# ArtFire.net
KiCad netlist of a schematic drawn in Altium Designer
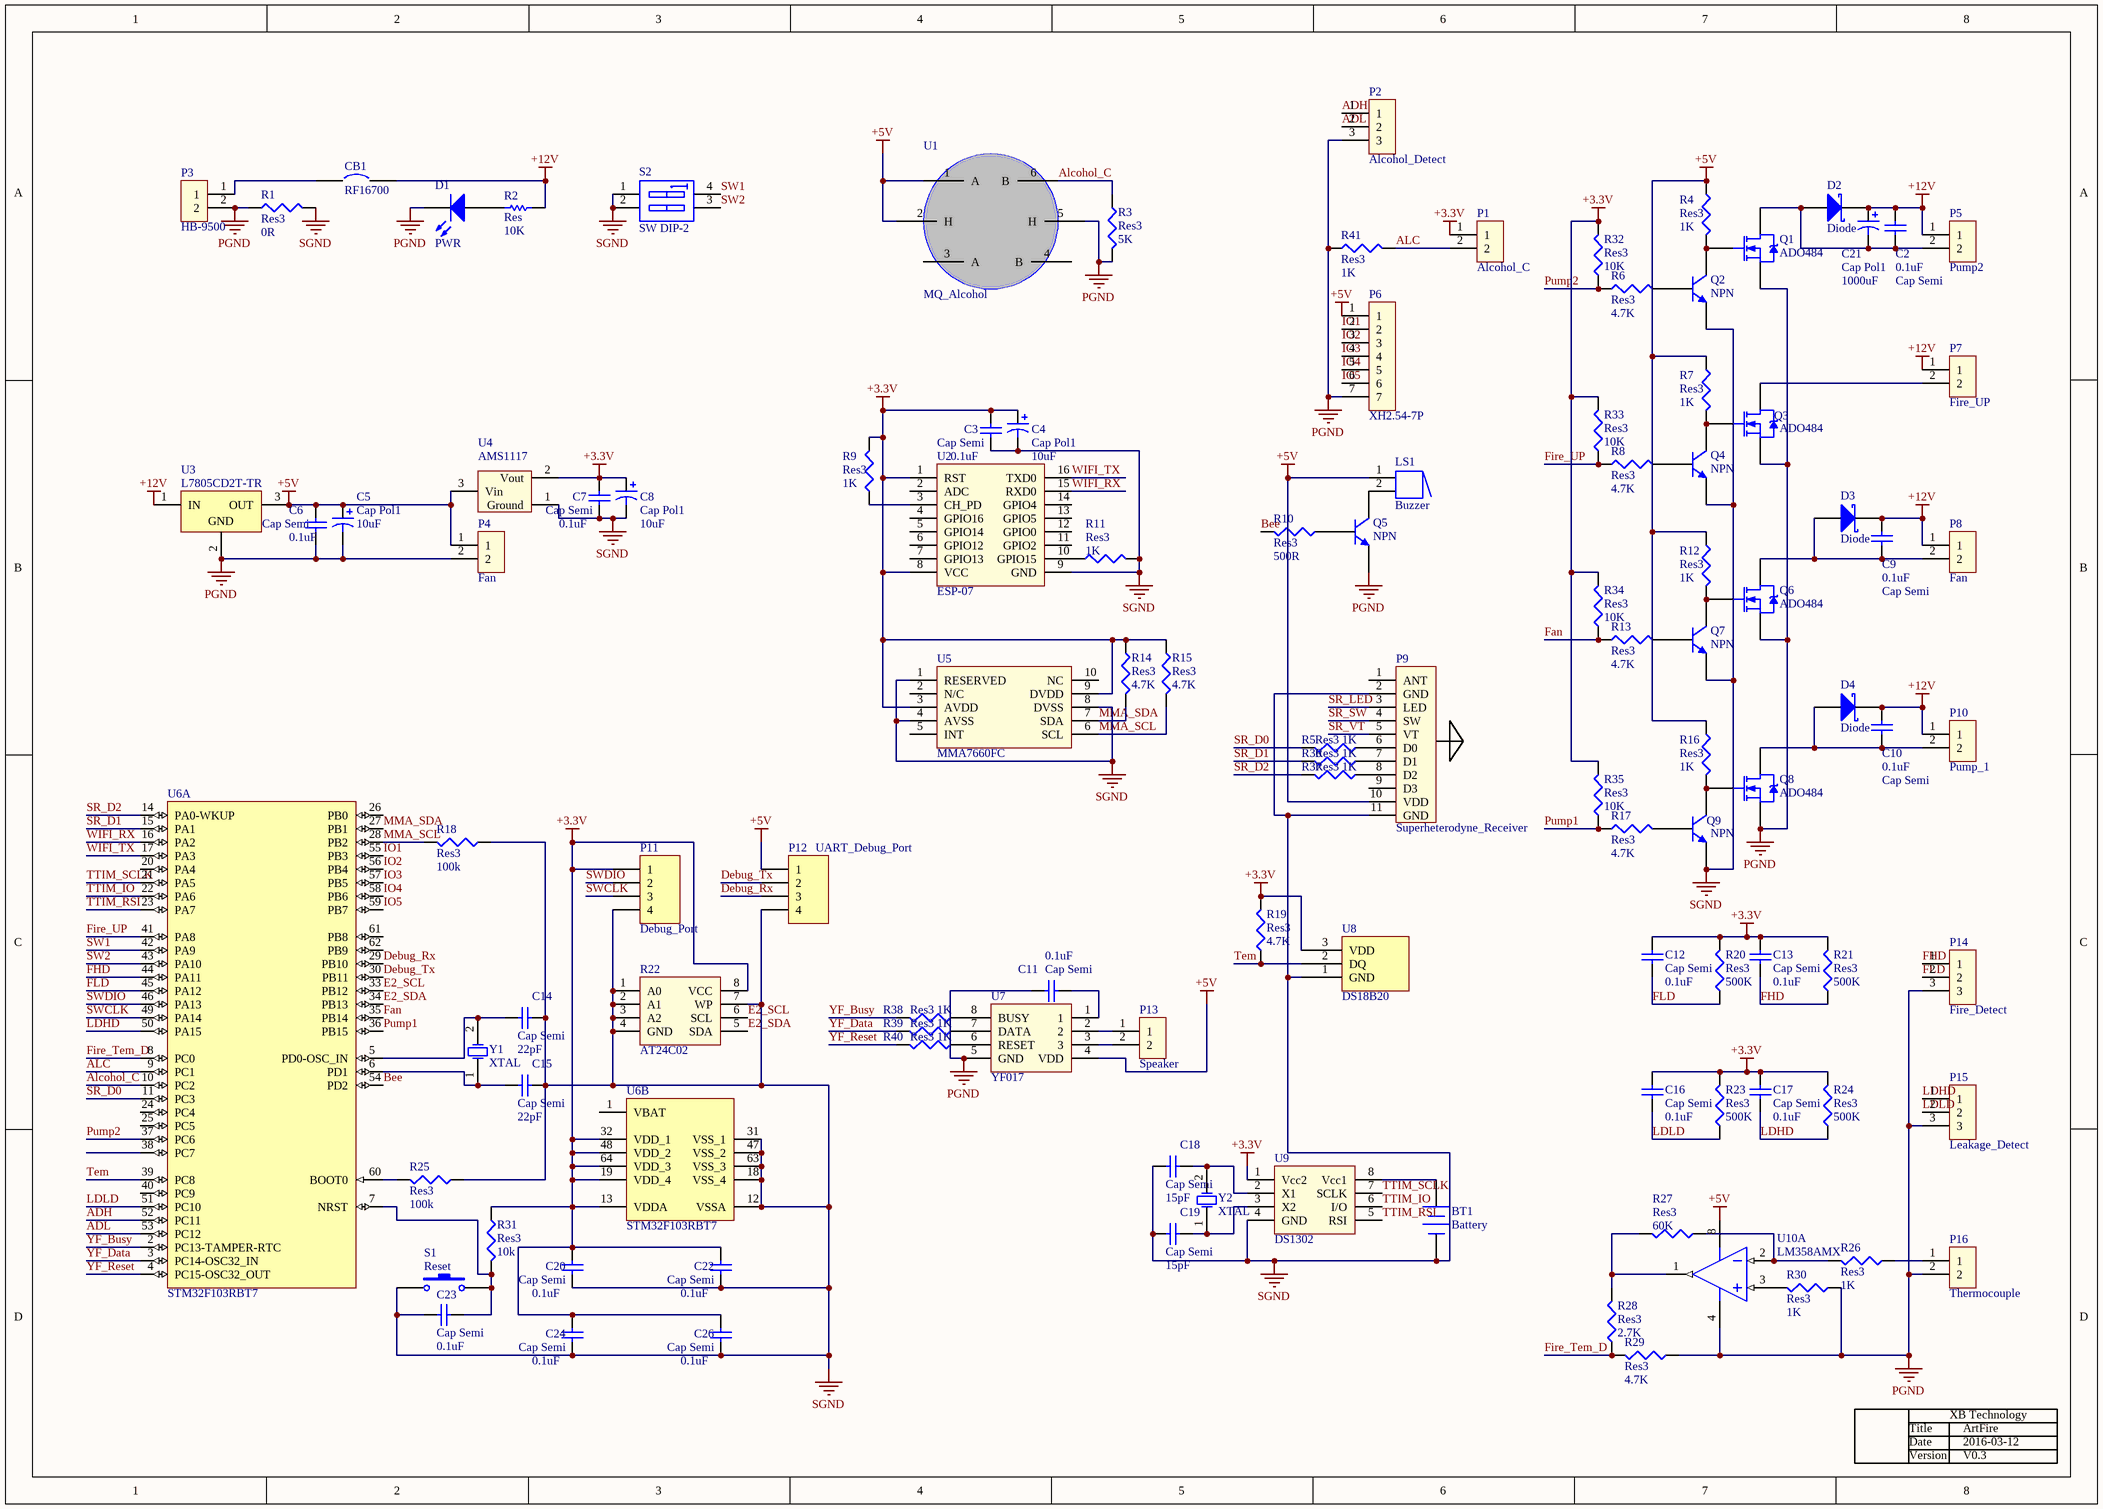
[diagram p0: ArtFire.SchDoc]

(export (version "E")
  (design (tool "Eeschema 10.0.6"))
  (components
    (comp (ref "BT1")
      (value "Battery")
      (footprint "Battery_1302")
      (description "Multicell Battery")
      (fields (field (name "PUBLISHER") "Altium Limited"))
      (libsource (lib "Miscellaneous Devices") (part "Battery"))
    )
    (comp (ref "C2")
      (value "Cap Semi")
      (footprint "6-0805_N")
      (description "Capacitor (Semiconductor SIM Model)")
      (fields (field (name "ALTIUM_VALUE") "0.1uF") (field (name "PUBLISHER") "Altium Limited"))
      (libsource (lib "Miscellaneous Devices") (part "Cap Semi"))
    )
    (comp (ref "C3")
      (value "Cap Semi")
      (footprint "6-0805_N")
      (description "Capacitor (Semiconductor SIM Model)")
      (fields (field (name "ALTIUM_VALUE") "0.1uF") (field (name "PUBLISHER") "Altium Limited"))
      (libsource (lib "Miscellaneous Devices") (part "Cap Semi"))
    )
    (comp (ref "C4")
      (value "Cap Pol1")
      (footprint "Cap_5*4mm")
      (description "Polarized Capacitor (Radial)")
      (fields (field (name "ALTIUM_VALUE") "10uF") (field (name "PUBLISHER") "Altium Limited"))
      (libsource (lib "Miscellaneous Devices") (part "Cap Pol1"))
    )
    (comp (ref "C5")
      (value "Cap Pol1")
      (footprint "Cap_5*4mm")
      (description "Polarized Capacitor (Radial)")
      (fields (field (name "ALTIUM_VALUE") "10uF") (field (name "PUBLISHER") "Altium Limited"))
      (libsource (lib "Miscellaneous Devices") (part "Cap Pol1"))
    )
    (comp (ref "C6")
      (value "Cap Semi")
      (footprint "6-0805_N")
      (description "Capacitor (Semiconductor SIM Model)")
      (fields (field (name "ALTIUM_VALUE") "0.1uF") (field (name "PUBLISHER") "Altium Limited"))
      (libsource (lib "Miscellaneous Devices") (part "Cap Semi"))
    )
    (comp (ref "C7")
      (value "Cap Semi")
      (footprint "6-0805_N")
      (description "Capacitor (Semiconductor SIM Model)")
      (fields (field (name "ALTIUM_VALUE") "0.1uF") (field (name "PUBLISHER") "Altium Limited"))
      (libsource (lib "Miscellaneous Devices") (part "Cap Semi"))
    )
    (comp (ref "C8")
      (value "Cap Pol1")
      (footprint "Cap_5*4mm")
      (description "Polarized Capacitor (Radial)")
      (fields (field (name "ALTIUM_VALUE") "10uF") (field (name "PUBLISHER") "Altium Limited"))
      (libsource (lib "Miscellaneous Devices") (part "Cap Pol1"))
    )
    (comp (ref "C9")
      (value "Cap Semi")
      (footprint "6-0805_N")
      (description "Capacitor (Semiconductor SIM Model)")
      (fields (field (name "ALTIUM_VALUE") "0.1uF") (field (name "PUBLISHER") "Altium Limited"))
      (libsource (lib "Miscellaneous Devices") (part "Cap Semi"))
    )
    (comp (ref "C10")
      (value "Cap Semi")
      (footprint "6-0805_N")
      (description "Capacitor (Semiconductor SIM Model)")
      (fields (field (name "ALTIUM_VALUE") "0.1uF") (field (name "PUBLISHER") "Altium Limited"))
      (libsource (lib "Miscellaneous Devices") (part "Cap Semi"))
    )
    (comp (ref "C11")
      (value "Cap Semi")
      (footprint "6-0805_N")
      (description "Capacitor (Semiconductor SIM Model)")
      (fields (field (name "ALTIUM_VALUE") "0.1uF") (field (name "PUBLISHER") "Altium Limited"))
      (libsource (lib "Miscellaneous Devices") (part "Cap Semi"))
    )
    (comp (ref "C12")
      (value "Cap Semi")
      (footprint "6-0805_N")
      (description "Capacitor (Semiconductor SIM Model)")
      (fields (field (name "ALTIUM_VALUE") "0.1uF") (field (name "PUBLISHER") "Altium Limited"))
      (libsource (lib "Miscellaneous Devices") (part "Cap Semi"))
    )
    (comp (ref "C13")
      (value "Cap Semi")
      (footprint "6-0805_N")
      (description "Capacitor (Semiconductor SIM Model)")
      (fields (field (name "ALTIUM_VALUE") "0.1uF") (field (name "PUBLISHER") "Altium Limited"))
      (libsource (lib "Miscellaneous Devices") (part "Cap Semi"))
    )
    (comp (ref "C14")
      (value "Cap Semi")
      (footprint "6-0805_N")
      (description "Capacitor (Semiconductor SIM Model)")
      (fields (field (name "ALTIUM_VALUE") "22pF") (field (name "PUBLISHER") "Altium Limited"))
      (libsource (lib "Miscellaneous Devices") (part "Cap Semi"))
    )
    (comp (ref "C15")
      (value "Cap Semi")
      (footprint "6-0805_N")
      (description "Capacitor (Semiconductor SIM Model)")
      (fields (field (name "ALTIUM_VALUE") "22pF") (field (name "PUBLISHER") "Altium Limited"))
      (libsource (lib "Miscellaneous Devices") (part "Cap Semi"))
    )
    (comp (ref "C16")
      (value "Cap Semi")
      (footprint "6-0805_N")
      (description "Capacitor (Semiconductor SIM Model)")
      (fields (field (name "ALTIUM_VALUE") "0.1uF") (field (name "PUBLISHER") "Altium Limited"))
      (libsource (lib "Miscellaneous Devices") (part "Cap Semi"))
    )
    (comp (ref "C17")
      (value "Cap Semi")
      (footprint "6-0805_N")
      (description "Capacitor (Semiconductor SIM Model)")
      (fields (field (name "ALTIUM_VALUE") "0.1uF") (field (name "PUBLISHER") "Altium Limited"))
      (libsource (lib "Miscellaneous Devices") (part "Cap Semi"))
    )
    (comp (ref "C18")
      (value "Cap Semi")
      (footprint "6-0805_N")
      (description "Capacitor (Semiconductor SIM Model)")
      (fields (field (name "ALTIUM_VALUE") "15pF") (field (name "PUBLISHER") "Altium Limited"))
      (libsource (lib "Miscellaneous Devices") (part "Cap Semi"))
    )
    (comp (ref "C19")
      (value "Cap Semi")
      (footprint "6-0805_N")
      (description "Capacitor (Semiconductor SIM Model)")
      (fields (field (name "ALTIUM_VALUE") "15pF") (field (name "PUBLISHER") "Altium Limited"))
      (libsource (lib "Miscellaneous Devices") (part "Cap Semi"))
    )
    (comp (ref "C20")
      (value "Cap Semi")
      (footprint "6-0805_N")
      (description "Capacitor (Semiconductor SIM Model)")
      (fields (field (name "ALTIUM_VALUE") "0.1uF") (field (name "PUBLISHER") "Altium Limited"))
      (libsource (lib "Miscellaneous Devices") (part "Cap Semi"))
    )
    (comp (ref "C21")
      (value "Cap Pol1")
      (footprint "CAP_10*10MM")
      (description "Polarized Capacitor (Radial)")
      (fields (field (name "ALTIUM_VALUE") "1000uF") (field (name "PUBLISHER") "Altium Limited"))
      (libsource (lib "Miscellaneous Devices") (part "Cap Pol1"))
    )
    (comp (ref "C22")
      (value "Cap Semi")
      (footprint "6-0805_N")
      (description "Capacitor (Semiconductor SIM Model)")
      (fields (field (name "ALTIUM_VALUE") "0.1uF") (field (name "PUBLISHER") "Altium Limited"))
      (libsource (lib "Miscellaneous Devices") (part "Cap Semi"))
    )
    (comp (ref "C23")
      (value "Cap Semi")
      (footprint "6-0805_N")
      (description "Capacitor (Semiconductor SIM Model)")
      (fields (field (name "ALTIUM_VALUE") "0.1uF") (field (name "PUBLISHER") "Altium Limited"))
      (libsource (lib "Miscellaneous Devices") (part "Cap Semi"))
    )
    (comp (ref "C24")
      (value "Cap Semi")
      (footprint "6-0805_N")
      (description "Capacitor (Semiconductor SIM Model)")
      (fields (field (name "ALTIUM_VALUE") "0.1uF") (field (name "PUBLISHER") "Altium Limited"))
      (libsource (lib "Miscellaneous Devices") (part "Cap Semi"))
    )
    (comp (ref "C26")
      (value "Cap Semi")
      (footprint "6-0805_N")
      (description "Capacitor (Semiconductor SIM Model)")
      (fields (field (name "ALTIUM_VALUE") "0.1uF") (field (name "PUBLISHER") "Altium Limited"))
      (libsource (lib "Miscellaneous Devices") (part "Cap Semi"))
    )
    (comp (ref "CB1")
      (value "RF16700")
      (footprint "SPST-2")
      (description "Circuit Breaker")
      (fields (field (name "PUBLISHER") "Altium Limited"))
      (libsource (lib "Miscellaneous Devices") (part "Circuit Breaker"))
    )
    (comp (ref "D1")
      (value "PWR")
      (footprint "6-0805_N")
      (description "Typical INFRARED GaAs LED")
      (fields (field (name "PUBLISHER") "Altium Limited"))
      (libsource (lib "Miscellaneous Devices") (part "LED0"))
    )
    (comp (ref "D2")
      (value "Diode")
      (footprint "US1M")
      (description "Silicon RF Schottky Diode for Mixer Applications in the VHF/UHF Range")
      (fields (field (name "PUBLISHER") "Altium Limited"))
      (libsource (lib "Miscellaneous Devices") (part "Diode BAT17"))
    )
    (comp (ref "D3")
      (value "Diode")
      (footprint "US1M")
      (description "Silicon RF Schottky Diode for Mixer Applications in the VHF/UHF Range")
      (fields (field (name "PUBLISHER") "Altium Limited"))
      (libsource (lib "Miscellaneous Devices") (part "Diode BAT17"))
    )
    (comp (ref "D4")
      (value "Diode")
      (footprint "US1M")
      (description "Silicon RF Schottky Diode for Mixer Applications in the VHF/UHF Range")
      (fields (field (name "PUBLISHER") "Altium Limited"))
      (libsource (lib "Miscellaneous Devices") (part "Diode BAT17"))
    )
    (comp (ref "LS1")
      (value "Buzzer")
      (footprint "BUZZER")
      (description "Magnetic Transducer Buzzer")
      (fields (field (name "PUBLISHER") "Altium Limited"))
      (libsource (lib "Miscellaneous Devices") (part "Buzzer"))
    )
    (comp (ref "P1")
      (value "Alcohol_C")
      (footprint "CH3.96_2P")
      (libsource (lib "CH3.96") (part "CH3.96_2P"))
    )
    (comp (ref "P2")
      (value "Alcohol_Detect")
      (footprint "XH2.54-3P")
      (libsource (lib "XH2.54") (part "XH2.54-3P"))
    )
    (comp (ref "P3")
      (value "HB-9500")
      (footprint "HB-9500")
      (description "High current connector")
      (libsource (lib "Simon'Library") (part "HB-9500"))
    )
    (comp (ref "P4") (value "Fan") (footprint "XH2.54-2P") (libsource (lib "XH2.54") (part "XH2.54-2P")))
    (comp (ref "P5") (value "Pump2") (footprint "CH3.96_2P") (libsource (lib "CH3.96") (part "CH3.96_2P")))
    (comp (ref "P6")
      (value "XH2.54-7P")
      (footprint "XH2.54-7P")
      (libsource (lib "XH2.54") (part "XH2.54-7P"))
    )
    (comp (ref "P7") (value "Fire_UP") (footprint "KF3.96_2P") (libsource (lib "KF3.96") (part "KF3.96")))
    (comp (ref "P8") (value "Fan") (footprint "XH2.54-2P") (libsource (lib "XH2.54") (part "XH2.54-2P")))
    (comp (ref "P9")
      (value "Superheterodyne_Receiver")
      (footprint "Sperheterodyne_Receiver")
      (libsource (lib "Simon'Library") (part "Superheterodyne_Receiver"))
    )
    (comp (ref "P10") (value "Pump_1") (footprint "CH3.96_2P") (libsource (lib "CH3.96") (part "CH3.96_2P")))
    (comp (ref "P11")
      (value "Debug_Port")
      (footprint "HDR1X4")
      (description "Header, 4-Pin")
      (fields (field (name "PUBLISHER") "Altium Limited"))
      (libsource (lib "Miscellaneous Connectors") (part "Header 4"))
    )
    (comp (ref "P12")
      (value "UART_Debug_Port")
      (footprint "HDR1X4")
      (description "Header, 4-Pin")
      (fields (field (name "PUBLISHER") "Altium Limited"))
      (libsource (lib "Miscellaneous Connectors") (part "Header 4"))
    )
    (comp (ref "P13") (value "Speaker") (footprint "XH2.54-2P") (libsource (lib "XH2.54") (part "XH2.54-2P")))
    (comp (ref "P14")
      (value "Fire_Detect")
      (footprint "CH3.96_3P")
      (libsource (lib "CH3.96") (part "CH3.96_3P"))
    )
    (comp (ref "P15")
      (value "Leakage_Detect")
      (footprint "XH2.54-3P")
      (libsource (lib "XH2.54") (part "XH2.54-3P"))
    )
    (comp (ref "P16")
      (value "Thermocouple")
      (footprint "CH3.96_2P")
      (libsource (lib "CH3.96") (part "CH3.96_2P"))
    )
    (comp (ref "Q1")
      (value "ADO484")
      (footprint "DPAK_AOD484")
      (description "N-Channel Power MOSFET")
      (fields (field (name "PUBLISHER") "Altium Limited"))
      (libsource (lib "Miscellaneous Devices") (part "NMOS-2"))
    )
    (comp (ref "Q2")
      (value "NPN")
      (footprint "SOT-23_N")
      (description "NPN Bipolar Transistor")
      (fields (field (name "PUBLISHER") "Altium Limited"))
      (libsource (lib "Miscellaneous Devices") (part "NPN"))
    )
    (comp (ref "Q3")
      (value "ADO484")
      (footprint "DPAK_AOD484")
      (description "N-Channel Power MOSFET")
      (fields (field (name "PUBLISHER") "Altium Limited"))
      (libsource (lib "Miscellaneous Devices") (part "NMOS-2"))
    )
    (comp (ref "Q4")
      (value "NPN")
      (footprint "SOT-23_N")
      (description "NPN Bipolar Transistor")
      (fields (field (name "PUBLISHER") "Altium Limited"))
      (libsource (lib "Miscellaneous Devices") (part "NPN"))
    )
    (comp (ref "Q5")
      (value "NPN")
      (footprint "SOT-23_N")
      (description "NPN Bipolar Transistor")
      (fields (field (name "PUBLISHER") "Altium Limited"))
      (libsource (lib "Miscellaneous Devices") (part "NPN"))
    )
    (comp (ref "Q6")
      (value "ADO484")
      (footprint "DPAK_AOD484")
      (description "N-Channel Power MOSFET")
      (fields (field (name "PUBLISHER") "Altium Limited"))
      (libsource (lib "Miscellaneous Devices") (part "NMOS-2"))
    )
    (comp (ref "Q7")
      (value "NPN")
      (footprint "SOT-23_N")
      (description "NPN Bipolar Transistor")
      (fields (field (name "PUBLISHER") "Altium Limited"))
      (libsource (lib "Miscellaneous Devices") (part "NPN"))
    )
    (comp (ref "Q8")
      (value "ADO484")
      (footprint "DPAK_AOD484")
      (description "N-Channel Power MOSFET")
      (fields (field (name "PUBLISHER") "Altium Limited"))
      (libsource (lib "Miscellaneous Devices") (part "NMOS-2"))
    )
    (comp (ref "Q9")
      (value "NPN")
      (footprint "SOT-23_N")
      (description "NPN Bipolar Transistor")
      (fields (field (name "PUBLISHER") "Altium Limited"))
      (libsource (lib "Miscellaneous Devices") (part "NPN"))
    )
    (comp (ref "R1")
      (value "Res3")
      (footprint "6-0805_N")
      (description "Resistor")
      (fields (field (name "ALTIUM_VALUE") "0R") (field (name "PUBLISHER") "Altium Limited"))
      (libsource (lib "Miscellaneous Devices") (part "Res3"))
    )
    (comp (ref "R2")
      (value "Res")
      (footprint "6-0805_N")
      (description "Resistor")
      (fields (field (name "ALTIUM_VALUE") "10K") (field (name "PUBLISHER") "Altium Limited"))
      (libsource (lib "Miscellaneous Devices") (part "Res1"))
    )
    (comp (ref "R3")
      (value "Res3")
      (footprint "6-0805_N")
      (description "Resistor")
      (fields (field (name "ALTIUM_VALUE") "5K") (field (name "PUBLISHER") "Altium Limited"))
      (libsource (lib "Miscellaneous Devices") (part "Res3"))
    )
    (comp (ref "R4")
      (value "Res3")
      (footprint "6-0805_N")
      (description "Resistor")
      (fields (field (name "ALTIUM_VALUE") "1K") (field (name "PUBLISHER") "Altium Limited"))
      (libsource (lib "Miscellaneous Devices") (part "Res3"))
    )
    (comp (ref "R5")
      (value "Res3")
      (footprint "6-0805_N")
      (description "Resistor")
      (fields (field (name "ALTIUM_VALUE") "1K") (field (name "PUBLISHER") "Altium Limited"))
      (libsource (lib "Miscellaneous Devices") (part "Res3"))
    )
    (comp (ref "R6")
      (value "Res3")
      (footprint "6-0805_N")
      (description "Resistor")
      (fields (field (name "ALTIUM_VALUE") "4.7K") (field (name "PUBLISHER") "Altium Limited"))
      (libsource (lib "Miscellaneous Devices") (part "Res3"))
    )
    (comp (ref "R7")
      (value "Res3")
      (footprint "6-0805_N")
      (description "Resistor")
      (fields (field (name "ALTIUM_VALUE") "1K") (field (name "PUBLISHER") "Altium Limited"))
      (libsource (lib "Miscellaneous Devices") (part "Res3"))
    )
    (comp (ref "R8")
      (value "Res3")
      (footprint "6-0805_N")
      (description "Resistor")
      (fields (field (name "ALTIUM_VALUE") "4.7K") (field (name "PUBLISHER") "Altium Limited"))
      (libsource (lib "Miscellaneous Devices") (part "Res3"))
    )
    (comp (ref "R9")
      (value "Res3")
      (footprint "6-0805_N")
      (description "Resistor")
      (fields (field (name "ALTIUM_VALUE") "1K") (field (name "PUBLISHER") "Altium Limited"))
      (libsource (lib "Miscellaneous Devices") (part "Res3"))
    )
    (comp (ref "R10")
      (value "Res3")
      (footprint "6-0805_N")
      (description "Resistor")
      (fields (field (name "ALTIUM_VALUE") "500R") (field (name "PUBLISHER") "Altium Limited"))
      (libsource (lib "Miscellaneous Devices") (part "Res3"))
    )
    (comp (ref "R11")
      (value "Res3")
      (footprint "6-0805_N")
      (description "Resistor")
      (fields (field (name "ALTIUM_VALUE") "1K") (field (name "PUBLISHER") "Altium Limited"))
      (libsource (lib "Miscellaneous Devices") (part "Res3"))
    )
    (comp (ref "R12")
      (value "Res3")
      (footprint "6-0805_N")
      (description "Resistor")
      (fields (field (name "ALTIUM_VALUE") "1K") (field (name "PUBLISHER") "Altium Limited"))
      (libsource (lib "Miscellaneous Devices") (part "Res3"))
    )
    (comp (ref "R13")
      (value "Res3")
      (footprint "6-0805_N")
      (description "Resistor")
      (fields (field (name "ALTIUM_VALUE") "4.7K") (field (name "PUBLISHER") "Altium Limited"))
      (libsource (lib "Miscellaneous Devices") (part "Res3"))
    )
    (comp (ref "R14")
      (value "Res3")
      (footprint "6-0805_N")
      (description "Resistor")
      (fields (field (name "ALTIUM_VALUE") "4.7K") (field (name "PUBLISHER") "Altium Limited"))
      (libsource (lib "Miscellaneous Devices") (part "Res3"))
    )
    (comp (ref "R15")
      (value "Res3")
      (footprint "6-0805_N")
      (description "Resistor")
      (fields (field (name "ALTIUM_VALUE") "4.7K") (field (name "PUBLISHER") "Altium Limited"))
      (libsource (lib "Miscellaneous Devices") (part "Res3"))
    )
    (comp (ref "R16")
      (value "Res3")
      (footprint "6-0805_N")
      (description "Resistor")
      (fields (field (name "ALTIUM_VALUE") "1K") (field (name "PUBLISHER") "Altium Limited"))
      (libsource (lib "Miscellaneous Devices") (part "Res3"))
    )
    (comp (ref "R17")
      (value "Res3")
      (footprint "6-0805_N")
      (description "Resistor")
      (fields (field (name "ALTIUM_VALUE") "4.7K") (field (name "PUBLISHER") "Altium Limited"))
      (libsource (lib "Miscellaneous Devices") (part "Res3"))
    )
    (comp (ref "R18")
      (value "Res3")
      (footprint "6-0805_N")
      (description "Resistor")
      (fields (field (name "ALTIUM_VALUE") "100k") (field (name "PUBLISHER") "Altium Limited"))
      (libsource (lib "Miscellaneous Devices") (part "Res3"))
    )
    (comp (ref "R19")
      (value "Res3")
      (footprint "6-0805_N")
      (description "Resistor")
      (fields (field (name "ALTIUM_VALUE") "4.7K") (field (name "PUBLISHER") "Altium Limited"))
      (libsource (lib "Miscellaneous Devices") (part "Res3"))
    )
    (comp (ref "R20")
      (value "Res3")
      (footprint "6-0805_N")
      (description "Resistor")
      (fields (field (name "ALTIUM_VALUE") "500K") (field (name "PUBLISHER") "Altium Limited"))
      (libsource (lib "Miscellaneous Devices") (part "Res3"))
    )
    (comp (ref "R21")
      (value "Res3")
      (footprint "6-0805_N")
      (description "Resistor")
      (fields (field (name "ALTIUM_VALUE") "500K") (field (name "PUBLISHER") "Altium Limited"))
      (libsource (lib "Miscellaneous Devices") (part "Res3"))
    )
    (comp (ref "R22")
      (value "AT24C02")
      (footprint "SOP8_TDA2822")
      (libsource (lib "Simon'Library") (part "AT24C02"))
    )
    (comp (ref "R23")
      (value "Res3")
      (footprint "6-0805_N")
      (description "Resistor")
      (fields (field (name "ALTIUM_VALUE") "500K") (field (name "PUBLISHER") "Altium Limited"))
      (libsource (lib "Miscellaneous Devices") (part "Res3"))
    )
    (comp (ref "R24")
      (value "Res3")
      (footprint "6-0805_N")
      (description "Resistor")
      (fields (field (name "ALTIUM_VALUE") "500K") (field (name "PUBLISHER") "Altium Limited"))
      (libsource (lib "Miscellaneous Devices") (part "Res3"))
    )
    (comp (ref "R25")
      (value "Res3")
      (footprint "6-0805_N")
      (description "Resistor")
      (fields (field (name "ALTIUM_VALUE") "100k") (field (name "PUBLISHER") "Altium Limited"))
      (libsource (lib "Miscellaneous Devices") (part "Res3"))
    )
    (comp (ref "R26")
      (value "Res3")
      (footprint "6-0805_N")
      (description "Resistor")
      (fields (field (name "ALTIUM_VALUE") "1K") (field (name "PUBLISHER") "Altium Limited"))
      (libsource (lib "Miscellaneous Devices") (part "Res3"))
    )
    (comp (ref "R27")
      (value "Res3")
      (footprint "6-0805_N")
      (description "Resistor")
      (fields (field (name "ALTIUM_VALUE") "60K") (field (name "PUBLISHER") "Altium Limited"))
      (libsource (lib "Miscellaneous Devices") (part "Res3"))
    )
    (comp (ref "R28")
      (value "Res3")
      (footprint "6-0805_N")
      (description "Resistor")
      (fields (field (name "ALTIUM_VALUE") "2.7K") (field (name "PUBLISHER") "Altium Limited"))
      (libsource (lib "Miscellaneous Devices") (part "Res3"))
    )
    (comp (ref "R29")
      (value "Res3")
      (footprint "6-0805_N")
      (description "Resistor")
      (fields (field (name "ALTIUM_VALUE") "4.7K") (field (name "PUBLISHER") "Altium Limited"))
      (libsource (lib "Miscellaneous Devices") (part "Res3"))
    )
    (comp (ref "R30")
      (value "Res3")
      (footprint "6-0805_N")
      (description "Resistor")
      (fields (field (name "ALTIUM_VALUE") "1K") (field (name "PUBLISHER") "Altium Limited"))
      (libsource (lib "Miscellaneous Devices") (part "Res3"))
    )
    (comp (ref "R31")
      (value "Res3")
      (footprint "6-0805_N")
      (description "Resistor")
      (fields (field (name "ALTIUM_VALUE") "10k") (field (name "PUBLISHER") "Altium Limited"))
      (libsource (lib "Miscellaneous Devices") (part "Res3"))
    )
    (comp (ref "R32")
      (value "Res3")
      (footprint "6-0805_N")
      (description "Resistor")
      (fields (field (name "ALTIUM_VALUE") "10K") (field (name "PUBLISHER") "Altium Limited"))
      (libsource (lib "Miscellaneous Devices") (part "Res3"))
    )
    (comp (ref "R33")
      (value "Res3")
      (footprint "6-0805_N")
      (description "Resistor")
      (fields (field (name "ALTIUM_VALUE") "10K") (field (name "PUBLISHER") "Altium Limited"))
      (libsource (lib "Miscellaneous Devices") (part "Res3"))
    )
    (comp (ref "R34")
      (value "Res3")
      (footprint "6-0805_N")
      (description "Resistor")
      (fields (field (name "ALTIUM_VALUE") "10K") (field (name "PUBLISHER") "Altium Limited"))
      (libsource (lib "Miscellaneous Devices") (part "Res3"))
    )
    (comp (ref "R35")
      (value "Res3")
      (footprint "6-0805_N")
      (description "Resistor")
      (fields (field (name "ALTIUM_VALUE") "10K") (field (name "PUBLISHER") "Altium Limited"))
      (libsource (lib "Miscellaneous Devices") (part "Res3"))
    )
    (comp (ref "R36")
      (value "Res3")
      (footprint "6-0805_N")
      (description "Resistor")
      (fields (field (name "ALTIUM_VALUE") "1K") (field (name "PUBLISHER") "Altium Limited"))
      (libsource (lib "Miscellaneous Devices") (part "Res3"))
    )
    (comp (ref "R37")
      (value "Res3")
      (footprint "6-0805_N")
      (description "Resistor")
      (fields (field (name "ALTIUM_VALUE") "1K") (field (name "PUBLISHER") "Altium Limited"))
      (libsource (lib "Miscellaneous Devices") (part "Res3"))
    )
    (comp (ref "R38")
      (value "Res3")
      (footprint "6-0805_N")
      (description "Resistor")
      (fields (field (name "ALTIUM_VALUE") "1K") (field (name "PUBLISHER") "Altium Limited"))
      (libsource (lib "Miscellaneous Devices") (part "Res3"))
    )
    (comp (ref "R39")
      (value "Res3")
      (footprint "6-0805_N")
      (description "Resistor")
      (fields (field (name "ALTIUM_VALUE") "1K") (field (name "PUBLISHER") "Altium Limited"))
      (libsource (lib "Miscellaneous Devices") (part "Res3"))
    )
    (comp (ref "R40")
      (value "Res3")
      (footprint "6-0805_N")
      (description "Resistor")
      (fields (field (name "ALTIUM_VALUE") "1K") (field (name "PUBLISHER") "Altium Limited"))
      (libsource (lib "Miscellaneous Devices") (part "Res3"))
    )
    (comp (ref "R41")
      (value "Res3")
      (footprint "6-0805_N")
      (description "Resistor")
      (fields (field (name "ALTIUM_VALUE") "1K") (field (name "PUBLISHER") "Altium Limited"))
      (libsource (lib "Miscellaneous Devices") (part "Res3"))
    )
    (comp (ref "S1")
      (value "Reset")
      (footprint "SWP_PB_6.5mm")
      (description "Switch")
      (fields (field (name "PUBLISHER") "Altium Limited"))
      (libsource (lib "Miscellaneous Devices") (part "SW-PB"))
    )
    (comp (ref "S2")
      (value "SW DIP-2")
      (footprint "DIP-4")
      (description "DIP Switch, 2 Position, SPST")
      (fields (field (name "PUBLISHER") "Altium Limited"))
      (libsource (lib "Miscellaneous Devices") (part "SW DIP-2"))
    )
    (comp (ref "U1") (value "MQ_Alcohol") (footprint "MQ") (libsource (lib "Simon'Library") (part "MQ")))
    (comp (ref "U2")
      (value "ESP-07")
      (footprint "ESP-07_Wifi")
      (libsource (lib "Simon'Library") (part "ESP-07_Wifi"))
    )
    (comp (ref "U3")
      (value "L7805CD2T-TR")
      (footprint "D2PAK_N")
      (description "Positive Voltage Regulator, 5V, 3-Pin TO-220")
      (libsource (lib "altium-import") (part "root_0_PM-REG-L4940-SIL3_"))
    )
    (comp (ref "U4")
      (value "AMS1117")
      (footprint "SOT223_N")
      (libsource (lib "Simon'Library") (part "AMS1117"))
    )
    (comp (ref "U5")
      (value "MMA7660FC")
      (footprint "DFN-10P")
      (libsource (lib "Simon'Library") (part "MMA7660FC"))
    )
    (comp (ref "U6")
      (value "STM32F103RBT7")
      (footprint "LQFP64_L")
      (libsource (lib "Altium Content Vault") (part "MC-ARM-STM32F101-SQ64"))
    )
    (comp (ref "U7") (value "YF017") (footprint "DIP-8") (libsource (lib "Simon'Library") (part "YF017")))
    (comp (ref "U8")
      (value "DS18B20")
      (footprint "TO-92A")
      (libsource (lib "Simon'Library") (part "DS18B20"))
    )
    (comp (ref "U9")
      (value "DS1302")
      (footprint "SOP8_TDA2822")
      (libsource (lib "Simon'Library") (part "DS1302"))
    )
    (comp (ref "U10")
      (value "LM358AMX")
      (footprint "M08A_M")
      (description "Low Power Dual Operational Amplifier, 8-pin Narrow SOIC")
      (fields (field (name "MANUFACTURER") "National Semiconductor"))
      (libsource (lib "Altium Content Vault") (part "AMP-OPA-LM158-8"))
    )
    (comp (ref "Y1")
      (value "XTAL")
      (footprint "XTAL")
      (description "Crystal Oscillator")
      (fields (field (name "PUBLISHER") "Altium Limited"))
      (libsource (lib "Miscellaneous Devices") (part "XTAL"))
    )
    (comp (ref "Y2")
      (value "XTAL")
      (footprint "32.768Cystal")
      (description "Crystal Oscillator")
      (fields (field (name "PUBLISHER") "Altium Limited"))
      (libsource (lib "Miscellaneous Devices") (part "XTAL"))
    )
  )
  (nets
    (net (code "1") (name "+3.3V") (class "Default")
      (node (ref "C12") (pin "2") (pinfunction "2_2") (pintype "passive"))
      (node (ref "C13") (pin "2") (pinfunction "2_2") (pintype "passive"))
      (node (ref "C16") (pin "2") (pinfunction "2_2") (pintype "passive"))
      (node (ref "C17") (pin "2") (pinfunction "2_2") (pintype "passive"))
      (node (ref "C20") (pin "1") (pinfunction "1_1") (pintype "passive"))
      (node (ref "C22") (pin "1") (pinfunction "1_1") (pintype "passive"))
      (node (ref "C24") (pin "1") (pinfunction "1_1") (pintype "passive"))
      (node (ref "C26") (pin "1") (pinfunction "1_1") (pintype "passive"))
      (node (ref "C3") (pin "1") (pinfunction "1_1") (pintype "passive"))
      (node (ref "C4") (pin "1") (pinfunction "1_1") (pintype "passive"))
      (node (ref "C7") (pin "1") (pinfunction "1_1") (pintype "passive"))
      (node (ref "C8") (pin "1") (pinfunction "1_1") (pintype "passive"))
      (node (ref "P1") (pin "1") (pinfunction "1_1") (pintype "passive"))
      (node (ref "P11") (pin "1") (pinfunction "1_1") (pintype "passive"))
      (node (ref "R14") (pin "1") (pinfunction "1_1") (pintype "passive"))
      (node (ref "R15") (pin "1") (pinfunction "1_1") (pintype "passive"))
      (node (ref "R19") (pin "2") (pinfunction "2_2") (pintype "passive"))
      (node (ref "R20") (pin "2") (pinfunction "2_2") (pintype "passive"))
      (node (ref "R21") (pin "2") (pinfunction "2_2") (pintype "passive"))
      (node (ref "R22") (pin "8") (pinfunction "VCC_8") (pintype "passive"))
      (node (ref "R23") (pin "2") (pinfunction "2_2") (pintype "passive"))
      (node (ref "R24") (pin "2") (pinfunction "2_2") (pintype "passive"))
      (node (ref "R31") (pin "1") (pinfunction "1_1") (pintype "passive"))
      (node (ref "R32") (pin "2") (pinfunction "2_2") (pintype "passive"))
      (node (ref "R33") (pin "2") (pinfunction "2_2") (pintype "passive"))
      (node (ref "R34") (pin "2") (pinfunction "2_2") (pintype "passive"))
      (node (ref "R35") (pin "2") (pinfunction "2_2") (pintype "passive"))
      (node (ref "R9") (pin "2") (pinfunction "2_2") (pintype "passive"))
      (node (ref "U2") (pin "1") (pinfunction "RST_1") (pintype "passive"))
      (node (ref "U2") (pin "8") (pinfunction "VCC_8") (pintype "passive"))
      (node (ref "U4") (pin "2") (pinfunction "Vout_2") (pintype "passive"))
      (node (ref "U5") (pin "3") (pinfunction "AVDD_3") (pintype "passive"))
      (node (ref "U5") (pin "9") (pinfunction "DVDD_9") (pintype "passive"))
      (node (ref "U6") (pin "13") (pinfunction "VDDA_13") (pintype "power_in"))
      (node (ref "U6") (pin "19") (pinfunction "VDD_4_19") (pintype "power_in"))
      (node (ref "U6") (pin "32") (pinfunction "VDD_1_32") (pintype "power_in"))
      (node (ref "U6") (pin "48") (pinfunction "VDD_2_48") (pintype "power_in"))
      (node (ref "U6") (pin "64") (pinfunction "VDD_3_64") (pintype "power_in"))
      (node (ref "U8") (pin "3") (pinfunction "VDD_3") (pintype "passive"))
      (node (ref "U9") (pin "1") (pinfunction "Vcc2_1") (pintype "passive"))
    )
    (net (code "2") (name "+5V") (class "Default")
      (node (ref "C5") (pin "1") (pinfunction "1_1") (pintype "passive"))
      (node (ref "C6") (pin "1") (pinfunction "1_1") (pintype "passive"))
      (node (ref "LS1") (pin "1") (pinfunction "1_1") (pintype "passive"))
      (node (ref "P12") (pin "1") (pinfunction "1_1") (pintype "passive"))
      (node (ref "P4") (pin "1") (pinfunction "1_1") (pintype "passive"))
      (node (ref "P6") (pin "1") (pinfunction "1_1") (pintype "passive"))
      (node (ref "P9") (pin "10") (pinfunction "VDD_10") (pintype "passive"))
      (node (ref "R12") (pin "1") (pinfunction "1_1") (pintype "passive"))
      (node (ref "R16") (pin "1") (pinfunction "1_1") (pintype "passive"))
      (node (ref "R4") (pin "1") (pinfunction "1_1") (pintype "passive"))
      (node (ref "R7") (pin "1") (pinfunction "1_1") (pintype "passive"))
      (node (ref "U1") (pin "1") (pinfunction "A_1") (pintype "passive"))
      (node (ref "U1") (pin "2") (pinfunction "H_2") (pintype "passive"))
      (node (ref "U10") (pin "8") (pinfunction "V+_8") (pintype "power_in"))
      (node (ref "U3") (pin "3") (pinfunction "OUT_3") (pintype "power_in"))
      (node (ref "U4") (pin "3") (pinfunction "Vin_3") (pintype "passive"))
      (node (ref "U7") (pin "4") (pinfunction "VDD_4") (pintype "passive"))
    )
    (net (code "3") (name "+12V") (class "Default")
      (node (ref "C10") (pin "1") (pinfunction "1_1") (pintype "passive"))
      (node (ref "C2") (pin "1") (pinfunction "1_1") (pintype "passive"))
      (node (ref "C21") (pin "1") (pinfunction "1_1") (pintype "passive"))
      (node (ref "C9") (pin "1") (pinfunction "1_1") (pintype "passive"))
      (node (ref "CB1") (pin "2") (pinfunction "2_2") (pintype "passive"))
      (node (ref "D2") (pin "2") (pinfunction "K_2") (pintype "passive"))
      (node (ref "D3") (pin "2") (pinfunction "K_2") (pintype "passive"))
      (node (ref "D4") (pin "2") (pinfunction "K_2") (pintype "passive"))
      (node (ref "P10") (pin "1") (pinfunction "1_1") (pintype "passive"))
      (node (ref "P5") (pin "1") (pinfunction "1_1") (pintype "passive"))
      (node (ref "P7") (pin "1") (pinfunction "1_1") (pintype "passive"))
      (node (ref "P8") (pin "1") (pinfunction "1_1") (pintype "passive"))
      (node (ref "R2") (pin "2") (pinfunction "2_2") (pintype "passive"))
      (node (ref "U3") (pin "1") (pinfunction "IN_1") (pintype "power_in"))
    )
    (net (code "4") (name "/ADH") (class "Default")
      (node (ref "P2") (pin "1") (pinfunction "1_1") (pintype "passive"))
      (node (ref "U6") (pin "52") (pinfunction "PC11_52") (pintype "bidirectional"))
    )
    (net (code "5") (name "/ADL") (class "Default")
      (node (ref "P2") (pin "2") (pinfunction "2_2") (pintype "passive"))
      (node (ref "U6") (pin "53") (pinfunction "PC12_53") (pintype "bidirectional"))
    )
    (net (code "6") (name "/ALC") (class "Default")
      (node (ref "P1") (pin "2") (pinfunction "2_2") (pintype "passive"))
      (node (ref "R41") (pin "2") (pinfunction "2_2") (pintype "passive"))
      (node (ref "U6") (pin "9") (pinfunction "PC1_9") (pintype "bidirectional"))
    )
    (net (code "7") (name "/Alcohol_C") (class "Default")
      (node (ref "R3") (pin "1") (pinfunction "1_1") (pintype "passive"))
      (node (ref "U1") (pin "6") (pinfunction "B_6") (pintype "passive"))
      (node (ref "U6") (pin "10") (pinfunction "PC2_10") (pintype "bidirectional"))
    )
    (net (code "8") (name "/Bee") (class "Default")
      (node (ref "R10") (pin "2") (pinfunction "2_2") (pintype "passive"))
      (node (ref "U6") (pin "54") (pinfunction "PD2_54") (pintype "bidirectional"))
    )
    (net (code "9") (name "/Debug_Rx") (class "Default")
      (node (ref "P12") (pin "3") (pinfunction "3_3") (pintype "passive"))
      (node (ref "U6") (pin "29") (pinfunction "PB10_29") (pintype "bidirectional"))
    )
    (net (code "10") (name "/Debug_Tx") (class "Default")
      (node (ref "P12") (pin "2") (pinfunction "2_2") (pintype "passive"))
      (node (ref "U6") (pin "30") (pinfunction "PB11_30") (pintype "bidirectional"))
    )
    (net (code "11") (name "/E2_SCL") (class "Default")
      (node (ref "R22") (pin "6") (pinfunction "SCL_6") (pintype "passive"))
      (node (ref "U6") (pin "33") (pinfunction "PB12_33") (pintype "bidirectional"))
    )
    (net (code "12") (name "/E2_SDA") (class "Default")
      (node (ref "R22") (pin "5") (pinfunction "SDA_5") (pintype "passive"))
      (node (ref "U6") (pin "34") (pinfunction "PB13_34") (pintype "bidirectional"))
    )
    (net (code "13") (name "/FHD") (class "Default")
      (node (ref "C13") (pin "1") (pinfunction "1_1") (pintype "passive"))
      (node (ref "P14") (pin "1") (pinfunction "1_1") (pintype "passive"))
      (node (ref "R21") (pin "1") (pinfunction "1_1") (pintype "passive"))
      (node (ref "U6") (pin "44") (pinfunction "PA11_44") (pintype "bidirectional"))
    )
    (net (code "14") (name "/FLD") (class "Default")
      (node (ref "C12") (pin "1") (pinfunction "1_1") (pintype "passive"))
      (node (ref "P14") (pin "2") (pinfunction "2_2") (pintype "passive"))
      (node (ref "R20") (pin "1") (pinfunction "1_1") (pintype "passive"))
      (node (ref "U6") (pin "45") (pinfunction "PA12_45") (pintype "bidirectional"))
    )
    (net (code "15") (name "/Fan") (class "Default")
      (node (ref "R13") (pin "1") (pinfunction "1_1") (pintype "passive"))
      (node (ref "R34") (pin "1") (pinfunction "1_1") (pintype "passive"))
      (node (ref "U6") (pin "35") (pinfunction "PB14_35") (pintype "bidirectional"))
    )
    (net (code "16") (name "/Fire_Tem_D") (class "Default")
      (node (ref "R28") (pin "1") (pinfunction "1_1") (pintype "passive"))
      (node (ref "R29") (pin "2") (pinfunction "2_2") (pintype "passive"))
      (node (ref "U6") (pin "8") (pinfunction "PC0_8") (pintype "bidirectional"))
    )
    (net (code "17") (name "/Fire_UP") (class "Default")
      (node (ref "R33") (pin "1") (pinfunction "1_1") (pintype "passive"))
      (node (ref "R8") (pin "1") (pinfunction "1_1") (pintype "passive"))
      (node (ref "U6") (pin "41") (pinfunction "PA8_41") (pintype "bidirectional"))
    )
    (net (code "18") (name "/IO1") (class "Default")
      (node (ref "P6") (pin "2") (pinfunction "2_2") (pintype "passive"))
      (node (ref "U6") (pin "55") (pinfunction "PB3_55") (pintype "bidirectional"))
    )
    (net (code "19") (name "/IO2") (class "Default")
      (node (ref "P6") (pin "3") (pinfunction "3_3") (pintype "passive"))
      (node (ref "U6") (pin "56") (pinfunction "PB4_56") (pintype "bidirectional"))
    )
    (net (code "20") (name "/IO3") (class "Default")
      (node (ref "P6") (pin "4") (pinfunction "4_4") (pintype "passive"))
      (node (ref "U6") (pin "57") (pinfunction "PB5_57") (pintype "bidirectional"))
    )
    (net (code "21") (name "/IO4") (class "Default")
      (node (ref "P6") (pin "5") (pinfunction "5_5") (pintype "passive"))
      (node (ref "U6") (pin "58") (pinfunction "PB6_58") (pintype "bidirectional"))
    )
    (net (code "22") (name "/IO5") (class "Default")
      (node (ref "P6") (pin "6") (pinfunction "6_6") (pintype "passive"))
      (node (ref "U6") (pin "59") (pinfunction "PB7_59") (pintype "bidirectional"))
    )
    (net (code "23") (name "/LDHD") (class "Default")
      (node (ref "C17") (pin "1") (pinfunction "1_1") (pintype "passive"))
      (node (ref "P15") (pin "1") (pinfunction "1_1") (pintype "passive"))
      (node (ref "R24") (pin "1") (pinfunction "1_1") (pintype "passive"))
      (node (ref "U6") (pin "50") (pinfunction "PA15_50") (pintype "bidirectional"))
    )
    (net (code "24") (name "/LDLD") (class "Default")
      (node (ref "C16") (pin "1") (pinfunction "1_1") (pintype "passive"))
      (node (ref "P15") (pin "2") (pinfunction "2_2") (pintype "passive"))
      (node (ref "R23") (pin "1") (pinfunction "1_1") (pintype "passive"))
      (node (ref "U6") (pin "51") (pinfunction "PC10_51") (pintype "bidirectional"))
    )
    (net (code "25") (name "/MMA_SCL") (class "Default")
      (node (ref "R15") (pin "2") (pinfunction "2_2") (pintype "passive"))
      (node (ref "R18") (pin "2") (pinfunction "2_2") (pintype "passive"))
      (node (ref "U5") (pin "6") (pinfunction "SCL_6") (pintype "passive"))
      (node (ref "U6") (pin "28") (pinfunction "PB2_28") (pintype "bidirectional"))
    )
    (net (code "26") (name "/MMA_SDA") (class "Default")
      (node (ref "R14") (pin "2") (pinfunction "2_2") (pintype "passive"))
      (node (ref "U5") (pin "7") (pinfunction "SDA_7") (pintype "passive"))
      (node (ref "U6") (pin "27") (pinfunction "PB1_27") (pintype "bidirectional"))
    )
    (net (code "27") (name "/Pump1") (class "Default")
      (node (ref "R17") (pin "1") (pinfunction "1_1") (pintype "passive"))
      (node (ref "R35") (pin "1") (pinfunction "1_1") (pintype "passive"))
      (node (ref "U6") (pin "36") (pinfunction "PB15_36") (pintype "bidirectional"))
    )
    (net (code "28") (name "/Pump2") (class "Default")
      (node (ref "R32") (pin "1") (pinfunction "1_1") (pintype "passive"))
      (node (ref "R6") (pin "1") (pinfunction "1_1") (pintype "passive"))
      (node (ref "U6") (pin "37") (pinfunction "PC6_37") (pintype "bidirectional"))
    )
    (net (code "29") (name "/SR_D0") (class "Default")
      (node (ref "R5") (pin "2") (pinfunction "2_2") (pintype "passive"))
      (node (ref "U6") (pin "11") (pinfunction "PC3_11") (pintype "bidirectional"))
    )
    (net (code "30") (name "/SR_D1") (class "Default")
      (node (ref "R36") (pin "2") (pinfunction "2_2") (pintype "passive"))
      (node (ref "U6") (pin "15") (pinfunction "PA1_15") (pintype "bidirectional"))
    )
    (net (code "31") (name "/SR_D2") (class "Default")
      (node (ref "R37") (pin "2") (pinfunction "2_2") (pintype "passive"))
      (node (ref "U6") (pin "14") (pinfunction "PA0-WKUP_14") (pintype "bidirectional"))
    )
    (net (code "32") (name "/SR_LED") (class "Default")
      (node (ref "P9") (pin "3") (pinfunction "LED_3") (pintype "passive"))
    )
    (net (code "33") (name "/SR_SW") (class "Default")
      (node (ref "P9") (pin "4") (pinfunction "SW_4") (pintype "passive"))
    )
    (net (code "34") (name "/SR_VT") (class "Default")
      (node (ref "P9") (pin "5") (pinfunction "VT_5") (pintype "passive"))
    )
    (net (code "35") (name "/SW1") (class "Default")
      (node (ref "S2") (pin "4") (pinfunction "B1_4") (pintype "passive"))
      (node (ref "U6") (pin "42") (pinfunction "PA9_42") (pintype "bidirectional"))
    )
    (net (code "36") (name "/SW2") (class "Default")
      (node (ref "S2") (pin "3") (pinfunction "B2_3") (pintype "passive"))
      (node (ref "U6") (pin "43") (pinfunction "PA10_43") (pintype "bidirectional"))
    )
    (net (code "37") (name "/SWCLK") (class "Default")
      (node (ref "P11") (pin "3") (pinfunction "3_3") (pintype "passive"))
      (node (ref "U6") (pin "49") (pinfunction "PA14_49") (pintype "bidirectional"))
    )
    (net (code "38") (name "/SWDIO") (class "Default")
      (node (ref "P11") (pin "2") (pinfunction "2_2") (pintype "passive"))
      (node (ref "U6") (pin "46") (pinfunction "PA13_46") (pintype "bidirectional"))
    )
    (net (code "39") (name "/TTIM_IO") (class "Default")
      (node (ref "U6") (pin "22") (pinfunction "PA6_22") (pintype "bidirectional"))
      (node (ref "U9") (pin "6") (pinfunction "I/O_6") (pintype "passive"))
    )
    (net (code "40") (name "/TTIM_RSI") (class "Default")
      (node (ref "U6") (pin "23") (pinfunction "PA7_23") (pintype "bidirectional"))
      (node (ref "U9") (pin "5") (pinfunction "RSI_5") (pintype "passive"))
    )
    (net (code "41") (name "/TTIM_SCLK") (class "Default")
      (node (ref "U6") (pin "21") (pinfunction "PA5_21") (pintype "bidirectional"))
      (node (ref "U9") (pin "7") (pinfunction "SCLK_7") (pintype "passive"))
    )
    (net (code "42") (name "/Tem") (class "Default")
      (node (ref "R19") (pin "1") (pinfunction "1_1") (pintype "passive"))
      (node (ref "U6") (pin "39") (pinfunction "PC8_39") (pintype "bidirectional"))
      (node (ref "U8") (pin "2") (pinfunction "DQ_2") (pintype "passive"))
    )
    (net (code "43") (name "/WIFI_RX") (class "Default")
      (node (ref "U2") (pin "15") (pinfunction "RXD0_15") (pintype "passive"))
      (node (ref "U6") (pin "16") (pinfunction "PA2_16") (pintype "bidirectional"))
    )
    (net (code "44") (name "/WIFI_TX") (class "Default")
      (node (ref "U2") (pin "16") (pinfunction "TXD0_16") (pintype "passive"))
      (node (ref "U6") (pin "17") (pinfunction "PA3_17") (pintype "bidirectional"))
    )
    (net (code "45") (name "/YF_Busy") (class "Default")
      (node (ref "R38") (pin "2") (pinfunction "2_2") (pintype "passive"))
      (node (ref "U6") (pin "2") (pinfunction "PC13-TAMPER-RTC_2") (pintype "bidirectional"))
    )
    (net (code "46") (name "/YF_Data") (class "Default")
      (node (ref "R39") (pin "2") (pinfunction "2_2") (pintype "passive"))
      (node (ref "U6") (pin "3") (pinfunction "PC14-OSC32_IN_3") (pintype "bidirectional"))
    )
    (net (code "47") (name "/YF_Reset") (class "Default")
      (node (ref "R40") (pin "2") (pinfunction "2_2") (pintype "passive"))
      (node (ref "U6") (pin "4") (pinfunction "PC15-OSC32_OUT_4") (pintype "bidirectional"))
    )
    (net (code "48") (name "Net-(BT1-+)") (class "Default")
      (node (ref "BT1") (pin "1") (pinfunction "+_1") (pintype "passive"))
      (node (ref "U9") (pin "8") (pinfunction "Vcc1_8") (pintype "passive"))
    )
    (net (code "49") (name "Net-(C11-Pad2)") (class "Default")
      (node (ref "C11") (pin "2") (pinfunction "2_2") (pintype "passive"))
      (node (ref "U7") (pin "1") (pinfunction "1_1") (pintype "passive"))
    )
    (net (code "50") (name "Net-(CB1-Pad1)") (class "Default")
      (node (ref "CB1") (pin "1") (pinfunction "1_1") (pintype "passive"))
      (node (ref "P3") (pin "1") (pinfunction "1_1") (pintype "passive"))
    )
    (net (code "51") (name "Net-(D1-A)") (class "Default")
      (node (ref "D1") (pin "1") (pinfunction "A_1") (pintype "passive"))
      (node (ref "R2") (pin "1") (pinfunction "1_1") (pintype "passive"))
    )
    (net (code "52") (name "Net-(D2-A)") (class "Default")
      (node (ref "C2") (pin "2") (pinfunction "2_2") (pintype "passive"))
      (node (ref "C21") (pin "2") (pinfunction "2_2") (pintype "passive"))
      (node (ref "D2") (pin "1") (pinfunction "A_1") (pintype "passive"))
      (node (ref "P5") (pin "2") (pinfunction "2_2") (pintype "passive"))
      (node (ref "Q1") (pin "2") (pinfunction "D_2") (pintype "passive"))
    )
    (net (code "53") (name "Net-(D3-A)") (class "Default")
      (node (ref "C9") (pin "2") (pinfunction "2_2") (pintype "passive"))
      (node (ref "D3") (pin "1") (pinfunction "A_1") (pintype "passive"))
      (node (ref "P8") (pin "2") (pinfunction "2_2") (pintype "passive"))
      (node (ref "Q6") (pin "2") (pinfunction "D_2") (pintype "passive"))
    )
    (net (code "54") (name "Net-(D4-A)") (class "Default")
      (node (ref "C10") (pin "2") (pinfunction "2_2") (pintype "passive"))
      (node (ref "D4") (pin "1") (pinfunction "A_1") (pintype "passive"))
      (node (ref "P10") (pin "2") (pinfunction "2_2") (pintype "passive"))
      (node (ref "Q8") (pin "2") (pinfunction "D_2") (pintype "passive"))
    )
    (net (code "55") (name "Net-(P9-D0)") (class "Default")
      (node (ref "P9") (pin "6") (pinfunction "D0_6") (pintype "passive"))
      (node (ref "R5") (pin "1") (pinfunction "1_1") (pintype "passive"))
    )
    (net (code "56") (name "Net-(P9-D1)") (class "Default")
      (node (ref "P9") (pin "7") (pinfunction "D1_7") (pintype "passive"))
      (node (ref "R36") (pin "1") (pinfunction "1_1") (pintype "passive"))
    )
    (net (code "57") (name "Net-(P9-D2)") (class "Default")
      (node (ref "P9") (pin "8") (pinfunction "D2_8") (pintype "passive"))
      (node (ref "R37") (pin "1") (pinfunction "1_1") (pintype "passive"))
    )
    (net (code "58") (name "Net-(P13-Pad1)") (class "Default")
      (node (ref "P13") (pin "1") (pinfunction "1_1") (pintype "passive"))
      (node (ref "U7") (pin "2") (pinfunction "2_2") (pintype "passive"))
    )
    (net (code "59") (name "Net-(P13-Pad2)") (class "Default")
      (node (ref "P13") (pin "2") (pinfunction "2_2") (pintype "passive"))
      (node (ref "U7") (pin "3") (pinfunction "3_3") (pintype "passive"))
    )
    (net (code "60") (name "Net-(P16-Pad1)") (class "Default")
      (node (ref "P16") (pin "1") (pinfunction "1_1") (pintype "passive"))
      (node (ref "R26") (pin "1") (pinfunction "1_1") (pintype "passive"))
    )
    (net (code "61") (name "Net-(Q1-G)") (class "Default")
      (node (ref "Q1") (pin "1") (pinfunction "G_1") (pintype "passive"))
      (node (ref "Q2") (pin "3") (pinfunction "C_3") (pintype "passive"))
      (node (ref "R4") (pin "2") (pinfunction "2_2") (pintype "passive"))
    )
    (net (code "62") (name "Net-(Q2-B)") (class "Default")
      (node (ref "Q2") (pin "1") (pinfunction "B_1") (pintype "passive"))
      (node (ref "R6") (pin "2") (pinfunction "2_2") (pintype "passive"))
    )
    (net (code "63") (name "Net-(Q3-D)") (class "Default")
      (node (ref "P7") (pin "2") (pinfunction "2_2") (pintype "passive"))
      (node (ref "Q3") (pin "2") (pinfunction "D_2") (pintype "passive"))
    )
    (net (code "64") (name "Net-(Q3-G)") (class "Default")
      (node (ref "Q3") (pin "1") (pinfunction "G_1") (pintype "passive"))
      (node (ref "Q4") (pin "3") (pinfunction "C_3") (pintype "passive"))
      (node (ref "R7") (pin "2") (pinfunction "2_2") (pintype "passive"))
    )
    (net (code "65") (name "Net-(Q4-B)") (class "Default")
      (node (ref "Q4") (pin "1") (pinfunction "B_1") (pintype "passive"))
      (node (ref "R8") (pin "2") (pinfunction "2_2") (pintype "passive"))
    )
    (net (code "66") (name "Net-(Q5-B)") (class "Default")
      (node (ref "Q5") (pin "1") (pinfunction "B_1") (pintype "passive"))
      (node (ref "R10") (pin "1") (pinfunction "1_1") (pintype "passive"))
    )
    (net (code "67") (name "Net-(Q5-C)") (class "Default")
      (node (ref "LS1") (pin "2") (pinfunction "2_2") (pintype "passive"))
      (node (ref "Q5") (pin "3") (pinfunction "C_3") (pintype "passive"))
    )
    (net (code "68") (name "Net-(Q6-G)") (class "Default")
      (node (ref "Q6") (pin "1") (pinfunction "G_1") (pintype "passive"))
      (node (ref "Q7") (pin "3") (pinfunction "C_3") (pintype "passive"))
      (node (ref "R12") (pin "2") (pinfunction "2_2") (pintype "passive"))
    )
    (net (code "69") (name "Net-(Q7-B)") (class "Default")
      (node (ref "Q7") (pin "1") (pinfunction "B_1") (pintype "passive"))
      (node (ref "R13") (pin "2") (pinfunction "2_2") (pintype "passive"))
    )
    (net (code "70") (name "Net-(Q8-G)") (class "Default")
      (node (ref "Q8") (pin "1") (pinfunction "G_1") (pintype "passive"))
      (node (ref "Q9") (pin "3") (pinfunction "C_3") (pintype "passive"))
      (node (ref "R16") (pin "2") (pinfunction "2_2") (pintype "passive"))
    )
    (net (code "71") (name "Net-(Q9-B)") (class "Default")
      (node (ref "Q9") (pin "1") (pinfunction "B_1") (pintype "passive"))
      (node (ref "R17") (pin "2") (pinfunction "2_2") (pintype "passive"))
    )
    (net (code "72") (name "Net-(U2-CH_PD)") (class "Default")
      (node (ref "R9") (pin "1") (pinfunction "1_1") (pintype "passive"))
      (node (ref "U2") (pin "3") (pinfunction "CH_PD_3") (pintype "passive"))
    )
    (net (code "73") (name "Net-(U2-GPIO15)") (class "Default")
      (node (ref "R11") (pin "1") (pinfunction "1_1") (pintype "passive"))
      (node (ref "U2") (pin "10") (pinfunction "GPIO15_10") (pintype "passive"))
    )
    (net (code "74") (name "Net-(U6A-BOOT0)") (class "Default")
      (node (ref "R25") (pin "2") (pinfunction "2_2") (pintype "passive"))
      (node (ref "U6") (pin "60") (pinfunction "BOOT0_60") (pintype "input"))
    )
    (net (code "75") (name "Net-(U6A-NRST)") (class "Default")
      (node (ref "C23") (pin "2") (pinfunction "2_2") (pintype "passive"))
      (node (ref "R31") (pin "2") (pinfunction "2_2") (pintype "passive"))
      (node (ref "S1") (pin "2") (pinfunction "2_2") (pintype "passive"))
      (node (ref "U6") (pin "7") (pinfunction "NRST_7") (pintype "bidirectional"))
    )
    (net (code "76") (name "Net-(U6A-PD0-OSC_IN)") (class "Default")
      (node (ref "C14") (pin "1") (pinfunction "1_1") (pintype "passive"))
      (node (ref "U6") (pin "5") (pinfunction "PD0-OSC_IN_5") (pintype "bidirectional"))
      (node (ref "Y1") (pin "2") (pinfunction "OSC2_2") (pintype "passive"))
    )
    (net (code "77") (name "Net-(U6A-PD1)") (class "Default")
      (node (ref "C15") (pin "1") (pinfunction "1_1") (pintype "passive"))
      (node (ref "U6") (pin "6") (pinfunction "PD1_6") (pintype "bidirectional"))
      (node (ref "Y1") (pin "1") (pinfunction "OSC1_1") (pintype "passive"))
    )
    (net (code "78") (name "Net-(U7-BUSY)") (class "Default")
      (node (ref "R38") (pin "1") (pinfunction "1_1") (pintype "passive"))
      (node (ref "U7") (pin "8") (pinfunction "BUSY_8") (pintype "passive"))
    )
    (net (code "79") (name "Net-(U7-DATA)") (class "Default")
      (node (ref "R39") (pin "1") (pinfunction "1_1") (pintype "passive"))
      (node (ref "U7") (pin "7") (pinfunction "DATA_7") (pintype "passive"))
    )
    (net (code "80") (name "Net-(U7-RESET)") (class "Default")
      (node (ref "R40") (pin "1") (pinfunction "1_1") (pintype "passive"))
      (node (ref "U7") (pin "6") (pinfunction "RESET_6") (pintype "passive"))
    )
    (net (code "81") (name "Net-(U9-X1)") (class "Default")
      (node (ref "C18") (pin "2") (pinfunction "2_2") (pintype "passive"))
      (node (ref "U9") (pin "2") (pinfunction "X1_2") (pintype "passive"))
      (node (ref "Y2") (pin "2") (pinfunction "OSC2_2") (pintype "passive"))
    )
    (net (code "82") (name "Net-(U9-X2)") (class "Default")
      (node (ref "C19") (pin "2") (pinfunction "2_2") (pintype "passive"))
      (node (ref "U9") (pin "3") (pinfunction "X2_3") (pintype "passive"))
      (node (ref "Y2") (pin "1") (pinfunction "OSC1_1") (pintype "passive"))
    )
    (net (code "83") (name "Net-(U10A-INA+)") (class "Default")
      (node (ref "R30") (pin "2") (pinfunction "2_2") (pintype "passive"))
      (node (ref "U10") (pin "3") (pinfunction "INA+_3") (pintype "input"))
    )
    (net (code "84") (name "Net-(U10A-INA-)") (class "Default")
      (node (ref "R26") (pin "2") (pinfunction "2_2") (pintype "passive"))
      (node (ref "R27") (pin "1") (pinfunction "1_1") (pintype "passive"))
      (node (ref "U10") (pin "2") (pinfunction "INA-_2") (pintype "input"))
    )
    (net (code "85") (name "Net-(U10A-OUTA)") (class "Default")
      (node (ref "R27") (pin "2") (pinfunction "2_2") (pintype "passive"))
      (node (ref "R28") (pin "2") (pinfunction "2_2") (pintype "passive"))
      (node (ref "U10") (pin "1") (pinfunction "OUTA_1") (pintype "output"))
    )
    (net (code "86") (name "PGND") (class "Default")
      (node (ref "C11") (pin "1") (pinfunction "1_1") (pintype "passive"))
      (node (ref "C5") (pin "2") (pinfunction "2_2") (pintype "passive"))
      (node (ref "C6") (pin "2") (pinfunction "2_2") (pintype "passive"))
      (node (ref "D1") (pin "2") (pinfunction "K_2") (pintype "passive"))
      (node (ref "P14") (pin "3") (pinfunction "3_3") (pintype "passive"))
      (node (ref "P15") (pin "3") (pinfunction "3_3") (pintype "passive"))
      (node (ref "P16") (pin "2") (pinfunction "2_2") (pintype "passive"))
      (node (ref "P2") (pin "3") (pinfunction "3_3") (pintype "passive"))
      (node (ref "P3") (pin "2") (pinfunction "2_2") (pintype "passive"))
      (node (ref "P4") (pin "2") (pinfunction "2_2") (pintype "passive"))
      (node (ref "P6") (pin "7") (pinfunction "7_7") (pintype "passive"))
      (node (ref "Q1") (pin "3") (pinfunction "S_3") (pintype "passive"))
      (node (ref "Q3") (pin "3") (pinfunction "S_3") (pintype "passive"))
      (node (ref "Q5") (pin "2") (pinfunction "E_2") (pintype "passive"))
      (node (ref "Q6") (pin "3") (pinfunction "S_3") (pintype "passive"))
      (node (ref "Q8") (pin "3") (pinfunction "S_3") (pintype "passive"))
      (node (ref "R1") (pin "1") (pinfunction "1_1") (pintype "passive"))
      (node (ref "R29") (pin "1") (pinfunction "1_1") (pintype "passive"))
      (node (ref "R3") (pin "2") (pinfunction "2_2") (pintype "passive"))
      (node (ref "R30") (pin "1") (pinfunction "1_1") (pintype "passive"))
      (node (ref "R41") (pin "1") (pinfunction "1_1") (pintype "passive"))
      (node (ref "U1") (pin "5") (pinfunction "H_5") (pintype "passive"))
      (node (ref "U10") (pin "4") (pinfunction "GND_4") (pintype "power_in"))
      (node (ref "U3") (pin "2") (pinfunction "GND_2") (pintype "power_in"))
      (node (ref "U7") (pin "5") (pinfunction "GND_5") (pintype "passive"))
    )
    (net (code "87") (name "SGND") (class "Default")
      (node (ref "BT1") (pin "2") (pinfunction "-_2") (pintype "passive"))
      (node (ref "C14") (pin "2") (pinfunction "2_2") (pintype "passive"))
      (node (ref "C15") (pin "2") (pinfunction "2_2") (pintype "passive"))
      (node (ref "C18") (pin "1") (pinfunction "1_1") (pintype "passive"))
      (node (ref "C19") (pin "1") (pinfunction "1_1") (pintype "passive"))
      (node (ref "C20") (pin "2") (pinfunction "2_2") (pintype "passive"))
      (node (ref "C22") (pin "2") (pinfunction "2_2") (pintype "passive"))
      (node (ref "C23") (pin "1") (pinfunction "1_1") (pintype "passive"))
      (node (ref "C24") (pin "2") (pinfunction "2_2") (pintype "passive"))
      (node (ref "C26") (pin "2") (pinfunction "2_2") (pintype "passive"))
      (node (ref "C3") (pin "2") (pinfunction "2_2") (pintype "passive"))
      (node (ref "C4") (pin "2") (pinfunction "2_2") (pintype "passive"))
      (node (ref "C7") (pin "2") (pinfunction "2_2") (pintype "passive"))
      (node (ref "C8") (pin "2") (pinfunction "2_2") (pintype "passive"))
      (node (ref "P11") (pin "4") (pinfunction "4_4") (pintype "passive"))
      (node (ref "P12") (pin "4") (pinfunction "4_4") (pintype "passive"))
      (node (ref "P9") (pin "11") (pinfunction "GND_11") (pintype "passive"))
      (node (ref "P9") (pin "2") (pinfunction "GND_2") (pintype "passive"))
      (node (ref "Q2") (pin "2") (pinfunction "E_2") (pintype "passive"))
      (node (ref "Q4") (pin "2") (pinfunction "E_2") (pintype "passive"))
      (node (ref "Q7") (pin "2") (pinfunction "E_2") (pintype "passive"))
      (node (ref "Q9") (pin "2") (pinfunction "E_2") (pintype "passive"))
      (node (ref "R1") (pin "2") (pinfunction "2_2") (pintype "passive"))
      (node (ref "R11") (pin "2") (pinfunction "2_2") (pintype "passive"))
      (node (ref "R18") (pin "1") (pinfunction "1_1") (pintype "passive"))
      (node (ref "R22") (pin "1") (pinfunction "A0_1") (pintype "passive"))
      (node (ref "R22") (pin "2") (pinfunction "A1_2") (pintype "passive"))
      (node (ref "R22") (pin "3") (pinfunction "A2_3") (pintype "passive"))
      (node (ref "R22") (pin "4") (pinfunction "GND_4") (pintype "passive"))
      (node (ref "R22") (pin "7") (pinfunction "WP_7") (pintype "passive"))
      (node (ref "R25") (pin "1") (pinfunction "1_1") (pintype "passive"))
      (node (ref "S1") (pin "1") (pinfunction "1_1") (pintype "passive"))
      (node (ref "S2") (pin "1") (pinfunction "A1_1") (pintype "passive"))
      (node (ref "S2") (pin "2") (pinfunction "A2_2") (pintype "passive"))
      (node (ref "U2") (pin "9") (pinfunction "GND_9") (pintype "passive"))
      (node (ref "U4") (pin "1") (pinfunction "Ground_1") (pintype "passive"))
      (node (ref "U5") (pin "1") (pinfunction "RESERVED_1") (pintype "passive"))
      (node (ref "U5") (pin "4") (pinfunction "AVSS_4") (pintype "passive"))
      (node (ref "U5") (pin "8") (pinfunction "DVSS_8") (pintype "passive"))
      (node (ref "U6") (pin "12") (pinfunction "VSSA_12") (pintype "power_in"))
      (node (ref "U6") (pin "18") (pinfunction "VSS_4_18") (pintype "power_in"))
      (node (ref "U6") (pin "31") (pinfunction "VSS_1_31") (pintype "power_in"))
      (node (ref "U6") (pin "47") (pinfunction "VSS_2_47") (pintype "power_in"))
      (node (ref "U6") (pin "63") (pinfunction "VSS_3_63") (pintype "power_in"))
      (node (ref "U8") (pin "1") (pinfunction "GND_1") (pintype "passive"))
      (node (ref "U9") (pin "4") (pinfunction "GND_4") (pintype "passive"))
    )
    (net (code "88") (name "unconnected-(P9-ANT-Pad1)") (class "Default")
      (node (ref "P9") (pin "1") (pinfunction "ANT_1") (pintype "passive"))
    )
    (net (code "89") (name "unconnected-(P9-D3-Pad9)") (class "Default")
      (node (ref "P9") (pin "9") (pinfunction "D3_9") (pintype "passive"))
    )
    (net (code "90") (name "unconnected-(U1-A-Pad3)") (class "Default")
      (node (ref "U1") (pin "3") (pinfunction "A_3") (pintype "passive"))
    )
    (net (code "91") (name "unconnected-(U1-B-Pad4)") (class "Default")
      (node (ref "U1") (pin "4") (pinfunction "B_4") (pintype "passive"))
    )
    (net (code "92") (name "unconnected-(U2-ADC-Pad2)") (class "Default")
      (node (ref "U2") (pin "2") (pinfunction "ADC_2") (pintype "passive"))
    )
    (net (code "93") (name "unconnected-(U2-GPIO0-Pad12)") (class "Default")
      (node (ref "U2") (pin "12") (pinfunction "GPIO0_12") (pintype "passive"))
    )
    (net (code "94") (name "unconnected-(U2-GPIO2-Pad11)") (class "Default")
      (node (ref "U2") (pin "11") (pinfunction "GPIO2_11") (pintype "passive"))
    )
    (net (code "95") (name "unconnected-(U2-GPIO4-Pad14)") (class "Default")
      (node (ref "U2") (pin "14") (pinfunction "GPIO4_14") (pintype "passive"))
    )
    (net (code "96") (name "unconnected-(U2-GPIO5-Pad13)") (class "Default")
      (node (ref "U2") (pin "13") (pinfunction "GPIO5_13") (pintype "passive"))
    )
    (net (code "97") (name "unconnected-(U2-GPIO12-Pad6)") (class "Default")
      (node (ref "U2") (pin "6") (pinfunction "GPIO12_6") (pintype "passive"))
    )
    (net (code "98") (name "unconnected-(U2-GPIO13-Pad7)") (class "Default")
      (node (ref "U2") (pin "7") (pinfunction "GPIO13_7") (pintype "passive"))
    )
    (net (code "99") (name "unconnected-(U2-GPIO14-Pad5)") (class "Default")
      (node (ref "U2") (pin "5") (pinfunction "GPIO14_5") (pintype "passive"))
    )
    (net (code "100") (name "unconnected-(U2-GPIO16-Pad4)") (class "Default")
      (node (ref "U2") (pin "4") (pinfunction "GPIO16_4") (pintype "passive"))
    )
    (net (code "101") (name "unconnected-(U5-INT-Pad5)") (class "Default")
      (node (ref "U5") (pin "5") (pinfunction "INT_5") (pintype "passive"))
    )
    (net (code "102") (name "unconnected-(U5-NC-Pad10)") (class "Default")
      (node (ref "U5") (pin "10") (pinfunction "NC_10") (pintype "passive"))
    )
    (net (code "103") (name "unconnected-(U5-N{slash}C-Pad2)") (class "Default")
      (node (ref "U5") (pin "2") (pinfunction "N/C_2") (pintype "passive"))
    )
    (net (code "104") (name "unconnected-(U6A-PA4-Pad20)") (class "Default")
      (node (ref "U6") (pin "20") (pinfunction "PA4_20") (pintype "bidirectional"))
    )
    (net (code "105") (name "unconnected-(U6A-PB0-Pad26)") (class "Default")
      (node (ref "U6") (pin "26") (pinfunction "PB0_26") (pintype "bidirectional"))
    )
    (net (code "106") (name "unconnected-(U6A-PB8-Pad61)") (class "Default")
      (node (ref "U6") (pin "61") (pinfunction "PB8_61") (pintype "bidirectional"))
    )
    (net (code "107") (name "unconnected-(U6A-PB9-Pad62)") (class "Default")
      (node (ref "U6") (pin "62") (pinfunction "PB9_62") (pintype "bidirectional"))
    )
    (net (code "108") (name "unconnected-(U6A-PC4-Pad24)") (class "Default")
      (node (ref "U6") (pin "24") (pinfunction "PC4_24") (pintype "bidirectional"))
    )
    (net (code "109") (name "unconnected-(U6A-PC5-Pad25)") (class "Default")
      (node (ref "U6") (pin "25") (pinfunction "PC5_25") (pintype "bidirectional"))
    )
    (net (code "110") (name "unconnected-(U6A-PC7-Pad38)") (class "Default")
      (node (ref "U6") (pin "38") (pinfunction "PC7_38") (pintype "bidirectional"))
    )
    (net (code "111") (name "unconnected-(U6A-PC9-Pad40)") (class "Default")
      (node (ref "U6") (pin "40") (pinfunction "PC9_40") (pintype "bidirectional"))
    )
    (net (code "112") (name "unconnected-(U6B-VBAT-Pad1)") (class "Default")
      (node (ref "U6") (pin "1") (pinfunction "VBAT_1") (pintype "power_in"))
    )
  )
)
